# Ephys.net
KiCad netlist of a schematic drawn in EAGLE
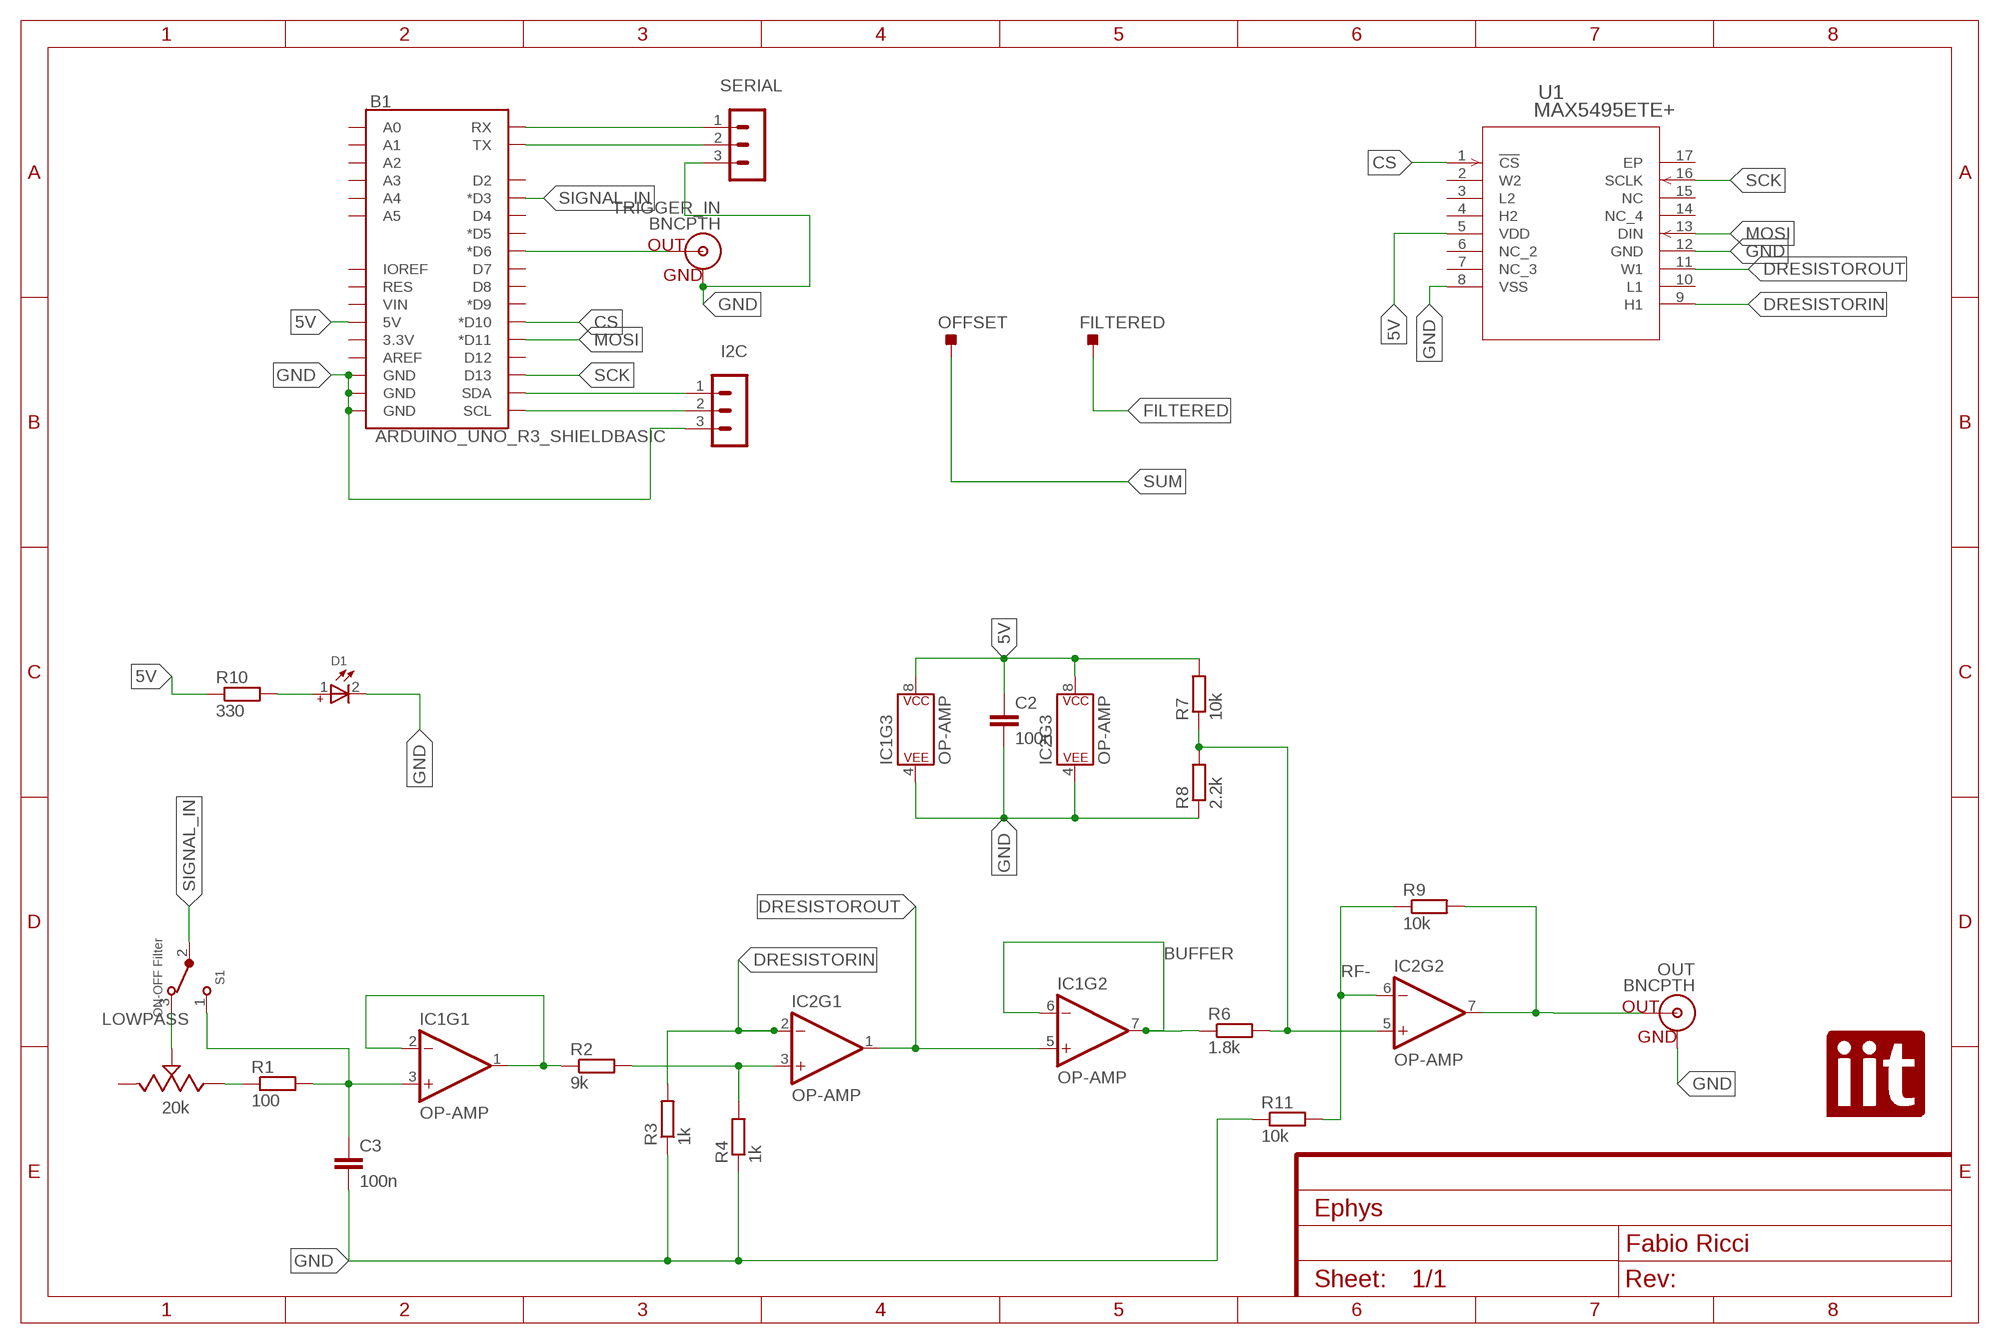
[diagram p0: schematic, sheet 1]

(export (version "E")
  (design (tool "Eeschema 10.0.6"))
  (components
    (comp (ref "B1")
      (value "ARDUINO_UNO_R3_SHIELDBASIC")
      (footprint "eagle-import:UNO_R3_SHIELD")
      (libsource (lib "eagle-import") (part "ARDUINO_UNO_R3_SHIELDBASIC"))
    )
    (comp (ref "C2")
      (value "100n")
      (footprint "eagle-import:C025-025X050")
      (libsource (lib "eagle-import") (part "C-EU025-025X050"))
    )
    (comp (ref "C3")
      (value "100n")
      (footprint "eagle-import:C025-025X050")
      (libsource (lib "eagle-import") (part "C-EU025-025X050"))
    )
    (comp (ref "D1")
      (value "WL-TMRC_3MM_151031SS04000_WITHOUTSTOPPER")
      (footprint "eagle-import:WL-TMRC_3MM")
      (libsource (lib "eagle-import") (part "WL-TMRC_3MM_WITHOUTSTOPPER_151031SS04000"))
    )
    (comp (ref "FILTERED")
      (value "TESTPOINT_TPS-PAD-036")
      (footprint "eagle-import:TESTPOINT_PAD-036")
      (libsource (lib "eagle-import") (part "TESTPOINT_TPS-PAD-036"))
    )
    (comp (ref "I2C")
      (value "MA03-1")
      (footprint "eagle-import:MA03-1")
      (libsource (lib "eagle-import") (part "MA03-1"))
    )
    (comp (ref "IC1")
      (value "OP-AMP")
      (footprint "eagle-import:DIP08")
      (libsource (lib "eagle-import") (part "OPAMP-DUALDIP"))
    )
    (comp (ref "IC2")
      (value "OP-AMP")
      (footprint "eagle-import:DIP08")
      (libsource (lib "eagle-import") (part "OPAMP-DUALDIP"))
    )
    (comp (ref "LOWPASS")
      (value "20k")
      (footprint "eagle-import:3362P-1-103LF")
      (fields
        (field (name "MANUFACTURER") "Bourns Inc.")
        (field (name "MPN") "3362P-1-103LF")
        (field (name "CREATED_PN") "PCBLayout.com")
      )
      (libsource (lib "eagle-import") (part "3362P-1-103LF"))
    )
    (comp (ref "OFFSET")
      (value "TESTPOINT_TPS-PAD-036")
      (footprint "eagle-import:TESTPOINT_PAD-036")
      (libsource (lib "eagle-import") (part "TESTPOINT_TPS-PAD-036"))
    )
    (comp (ref "OUT")
      (value "BNCPTH")
      (footprint "eagle-import:BNC")
      (libsource (lib "eagle-import") (part "BNCPTH"))
    )
    (comp (ref "R1")
      (value "100")
      (footprint "eagle-import:0204_7")
      (libsource (lib "eagle-import") (part "R-EU_0204/7"))
    )
    (comp (ref "R2")
      (value "9k")
      (footprint "eagle-import:0204_7")
      (libsource (lib "eagle-import") (part "R-EU_0204/7"))
    )
    (comp (ref "R3")
      (value "1k")
      (footprint "eagle-import:0204_7")
      (libsource (lib "eagle-import") (part "R-EU_0204/7"))
    )
    (comp (ref "R4")
      (value "1k")
      (footprint "eagle-import:0204_7")
      (libsource (lib "eagle-import") (part "R-EU_0204/7"))
    )
    (comp (ref "R6")
      (value "1.8k")
      (footprint "eagle-import:0204_7")
      (libsource (lib "eagle-import") (part "R-EU_0204/7"))
    )
    (comp (ref "R7")
      (value "10k")
      (footprint "eagle-import:0204_7")
      (libsource (lib "eagle-import") (part "R-EU_0204/7"))
    )
    (comp (ref "R8")
      (value "2.2k")
      (footprint "eagle-import:0204_7")
      (libsource (lib "eagle-import") (part "R-EU_0204/7"))
    )
    (comp (ref "R9")
      (value "10k")
      (footprint "eagle-import:0204_7")
      (libsource (lib "eagle-import") (part "R-EU_0204/7"))
    )
    (comp (ref "R10")
      (value "330")
      (footprint "eagle-import:0204_7")
      (libsource (lib "eagle-import") (part "R-EU_0204/7"))
    )
    (comp (ref "R11")
      (value "10k")
      (footprint "eagle-import:0204_7")
      (libsource (lib "eagle-import") (part "R-EU_0204/7"))
    )
    (comp (ref "S1")
      (value "ON-OFF Filter")
      (footprint "eagle-import:472121010111")
      (libsource (lib "eagle-import") (part "472121010111"))
    )
    (comp (ref "SERIAL")
      (value "MA03-1")
      (footprint "eagle-import:MA03-1")
      (libsource (lib "eagle-import") (part "MA03-1"))
    )
    (comp (ref "TRIGGER_IN")
      (value "BNCPTH")
      (footprint "eagle-import:BNC")
      (libsource (lib "eagle-import") (part "BNCPTH"))
    )
    (comp (ref "U$1")
      (value "LOGO")
      (footprint "eagle-import:IIT")
      (libsource (lib "eagle-import") (part "LOGO"))
    )
    (comp (ref "U1")
      (value "MAX5495ETE+")
      (footprint "eagle-import:21-0140_T1655+3_MXM")
      (fields (field (name "COPYRIGHT") "Copyright (C) 2024 Ultra Librarian. All rights reserved."))
      (libsource (lib "eagle-import") (part "MAX5495ETE+"))
    )
  )
  (nets
    (net (code "1") (name "/BUFFER") (class "Default")
      (node (ref "IC1") (pin "6") (pinfunction "-IN_6") (pintype "input"))
      (node (ref "IC1") (pin "7") (pinfunction "OUT_7") (pintype "output"))
      (node (ref "R6") (pin "1") (pinfunction "1_1") (pintype "passive"))
    )
    (net (code "2") (name "/RF-") (class "Default")
      (node (ref "IC2") (pin "6") (pinfunction "-IN_6") (pintype "input"))
      (node (ref "R11") (pin "2") (pinfunction "2_2") (pintype "passive"))
      (node (ref "R9") (pin "1") (pinfunction "1_1") (pintype "passive"))
    )
    (net (code "3") (name "5V") (class "Default")
      (node (ref "B1") (pin "5V") (pinfunction "5V_5V") (pintype "bidirectional"))
      (node (ref "C2") (pin "1") (pinfunction "1_1") (pintype "passive"))
      (node (ref "IC1") (pin "8") (pinfunction "P$V+_8") (pintype "bidirectional"))
      (node (ref "IC2") (pin "8") (pinfunction "P$V+_8") (pintype "bidirectional"))
      (node (ref "R10") (pin "1") (pinfunction "1_1") (pintype "passive"))
      (node (ref "R7") (pin "2") (pinfunction "2_2") (pintype "passive"))
      (node (ref "U1") (pin "5") (pinfunction "VDD_5") (pintype "power_in"))
    )
    (net (code "4") (name "CS") (class "Default")
      (node (ref "B1") (pin "D10") (pinfunction "*D10_D10") (pintype "bidirectional"))
      (node (ref "U1") (pin "1") (pinfunction "~{CS}_1") (pintype "input"))
    )
    (net (code "5") (name "DRESISTORIN") (class "Default")
      (node (ref "IC2") (pin "2") (pinfunction "-IN_2") (pintype "input"))
      (node (ref "R3") (pin "2") (pinfunction "2_2") (pintype "passive"))
      (node (ref "U1") (pin "9") (pinfunction "H1_9") (pintype "passive"))
    )
    (net (code "6") (name "DRESISTOROUT") (class "Default")
      (node (ref "IC1") (pin "5") (pinfunction "+IN_5") (pintype "input"))
      (node (ref "IC2") (pin "1") (pinfunction "OUT_1") (pintype "output"))
      (node (ref "U1") (pin "11") (pinfunction "W1_11") (pintype "passive"))
    )
    (net (code "7") (name "FILTERED") (class "Default")
      (node (ref "C3") (pin "1") (pinfunction "1_1") (pintype "passive"))
      (node (ref "FILTERED") (pin "1") (pinfunction "TP_1") (pintype "passive"))
      (node (ref "IC1") (pin "3") (pinfunction "+IN_3") (pintype "input"))
      (node (ref "R1") (pin "2") (pinfunction "2_2") (pintype "passive"))
      (node (ref "S1") (pin "1") (pinfunction "1_1") (pintype "passive"))
    )
    (net (code "8") (name "GND") (class "Default")
      (node (ref "B1") (pin "GND@0") (pinfunction "GND_GND@0") (pintype "bidirectional"))
      (node (ref "B1") (pin "GND@1") (pinfunction "GND_GND@1") (pintype "bidirectional"))
      (node (ref "B1") (pin "GND@2") (pinfunction "GND_GND@2") (pintype "bidirectional"))
      (node (ref "C2") (pin "2") (pinfunction "2_2") (pintype "passive"))
      (node (ref "C3") (pin "2") (pinfunction "2_2") (pintype "passive"))
      (node (ref "D1") (pin "2") (pinfunction "-_2") (pintype "passive"))
      (node (ref "I2C") (pin "3") (pinfunction "3_3") (pintype "passive"))
      (node (ref "IC1") (pin "4") (pinfunction "P$V-_4") (pintype "bidirectional"))
      (node (ref "IC2") (pin "4") (pinfunction "P$V-_4") (pintype "bidirectional"))
      (node (ref "OUT") (pin "GND") (pinfunction "GND_GND") (pintype "bidirectional"))
      (node (ref "R11") (pin "1") (pinfunction "1_1") (pintype "passive"))
      (node (ref "R3") (pin "1") (pinfunction "1_1") (pintype "passive"))
      (node (ref "R4") (pin "1") (pinfunction "1_1") (pintype "passive"))
      (node (ref "R8") (pin "1") (pinfunction "1_1") (pintype "passive"))
      (node (ref "SERIAL") (pin "3") (pinfunction "3_3") (pintype "passive"))
      (node (ref "TRIGGER_IN") (pin "GND") (pinfunction "GND_GND") (pintype "bidirectional"))
      (node (ref "U1") (pin "12") (pinfunction "GND_12") (pintype "power_in"))
      (node (ref "U1") (pin "8") (pinfunction "VSS_8") (pintype "power_in"))
    )
    (net (code "9") (name "MOSI") (class "Default")
      (node (ref "B1") (pin "D11") (pinfunction "*D11_D11") (pintype "bidirectional"))
      (node (ref "U1") (pin "13") (pinfunction "DIN_13") (pintype "input"))
    )
    (net (code "10") (name "Net-(B1-*D6)") (class "Default")
      (node (ref "B1") (pin "D6") (pinfunction "*D6_D6") (pintype "bidirectional"))
      (node (ref "TRIGGER_IN") (pin "S") (pinfunction "OUT_S") (pintype "bidirectional"))
    )
    (net (code "11") (name "Net-(B1-PadRX)") (class "Default")
      (node (ref "B1") (pin "RX") (pinfunction "RX_RX") (pintype "bidirectional"))
      (node (ref "SERIAL") (pin "1") (pinfunction "1_1") (pintype "passive"))
    )
    (net (code "12") (name "Net-(B1-PadSCL)") (class "Default")
      (node (ref "B1") (pin "SCL") (pinfunction "SCL_SCL") (pintype "bidirectional"))
      (node (ref "I2C") (pin "2") (pinfunction "2_2") (pintype "passive"))
    )
    (net (code "13") (name "Net-(B1-PadSDA)") (class "Default")
      (node (ref "B1") (pin "SDA") (pinfunction "SDA_SDA") (pintype "bidirectional"))
      (node (ref "I2C") (pin "1") (pinfunction "1_1") (pintype "passive"))
    )
    (net (code "14") (name "Net-(B1-PadTX)") (class "Default")
      (node (ref "B1") (pin "TX") (pinfunction "TX_TX") (pintype "bidirectional"))
      (node (ref "SERIAL") (pin "2") (pinfunction "2_2") (pintype "passive"))
    )
    (net (code "15") (name "Net-(D1-+)") (class "Default")
      (node (ref "D1") (pin "1") (pinfunction "+_1") (pintype "passive"))
      (node (ref "R10") (pin "2") (pinfunction "2_2") (pintype "passive"))
    )
    (net (code "16") (name "Net-(IC1A--IN)") (class "Default")
      (node (ref "IC1") (pin "1") (pinfunction "OUT_1") (pintype "output"))
      (node (ref "IC1") (pin "2") (pinfunction "-IN_2") (pintype "input"))
      (node (ref "R2") (pin "1") (pinfunction "1_1") (pintype "passive"))
    )
    (net (code "17") (name "Net-(IC2A-+IN)") (class "Default")
      (node (ref "IC2") (pin "3") (pinfunction "+IN_3") (pintype "input"))
      (node (ref "R2") (pin "2") (pinfunction "2_2") (pintype "passive"))
      (node (ref "R4") (pin "2") (pinfunction "2_2") (pintype "passive"))
    )
    (net (code "18") (name "Net-(IC2B-OUT)") (class "Default")
      (node (ref "IC2") (pin "7") (pinfunction "OUT_7") (pintype "output"))
      (node (ref "OUT") (pin "S") (pinfunction "OUT_S") (pintype "bidirectional"))
      (node (ref "R9") (pin "2") (pinfunction "2_2") (pintype "passive"))
    )
    (net (code "19") (name "Net-(LOWPASS-Pad2)") (class "Default")
      (node (ref "LOWPASS") (pin "2") (pinfunction "2_2") (pintype "passive"))
      (node (ref "S1") (pin "3") (pinfunction "3_3") (pintype "passive"))
    )
    (net (code "20") (name "Net-(LOWPASS-Pad3)") (class "Default")
      (node (ref "LOWPASS") (pin "3") (pinfunction "3_3") (pintype "passive"))
      (node (ref "R1") (pin "1") (pinfunction "1_1") (pintype "passive"))
    )
    (net (code "21") (name "SCK") (class "Default")
      (node (ref "B1") (pin "D13") (pinfunction "D13_D13") (pintype "bidirectional"))
      (node (ref "U1") (pin "16") (pinfunction "SCLK_16") (pintype "input"))
    )
    (net (code "22") (name "SIGNAL_IN") (class "Default")
      (node (ref "B1") (pin "D3") (pinfunction "*D3_D3") (pintype "bidirectional"))
      (node (ref "S1") (pin "2") (pinfunction "2_2") (pintype "passive"))
    )
    (net (code "23") (name "SUM") (class "Default")
      (node (ref "IC2") (pin "5") (pinfunction "+IN_5") (pintype "input"))
      (node (ref "OFFSET") (pin "1") (pinfunction "TP_1") (pintype "passive"))
      (node (ref "R6") (pin "2") (pinfunction "2_2") (pintype "passive"))
      (node (ref "R7") (pin "1") (pinfunction "1_1") (pintype "passive"))
      (node (ref "R8") (pin "2") (pinfunction "2_2") (pintype "passive"))
    )
    (net (code "24") (name "unconnected-(B1-*D5-PadD5)") (class "Default")
      (node (ref "B1") (pin "D5") (pinfunction "*D5_D5") (pintype "bidirectional"))
    )
    (net (code "25") (name "unconnected-(B1-*D9-PadD9)") (class "Default")
      (node (ref "B1") (pin "D9") (pinfunction "*D9_D9") (pintype "bidirectional"))
    )
    (net (code "26") (name "unconnected-(B1-Pad3.3V)") (class "Default")
      (node (ref "B1") (pin "3.3V") (pinfunction "3.3V_3.3V") (pintype "bidirectional"))
    )
    (net (code "27") (name "unconnected-(B1-PadA0)") (class "Default")
      (node (ref "B1") (pin "A0") (pinfunction "A0_A0") (pintype "bidirectional"))
    )
    (net (code "28") (name "unconnected-(B1-PadA1)") (class "Default")
      (node (ref "B1") (pin "A1") (pinfunction "A1_A1") (pintype "bidirectional"))
    )
    (net (code "29") (name "unconnected-(B1-PadA2)") (class "Default")
      (node (ref "B1") (pin "A2") (pinfunction "A2_A2") (pintype "bidirectional"))
    )
    (net (code "30") (name "unconnected-(B1-PadA3)") (class "Default")
      (node (ref "B1") (pin "A3") (pinfunction "A3_A3") (pintype "bidirectional"))
    )
    (net (code "31") (name "unconnected-(B1-PadA4)") (class "Default")
      (node (ref "B1") (pin "A4") (pinfunction "A4_A4") (pintype "bidirectional"))
    )
    (net (code "32") (name "unconnected-(B1-PadA5)") (class "Default")
      (node (ref "B1") (pin "A5") (pinfunction "A5_A5") (pintype "bidirectional"))
    )
    (net (code "33") (name "unconnected-(B1-PadAREF)") (class "Default")
      (node (ref "B1") (pin "AREF") (pinfunction "AREF_AREF") (pintype "bidirectional"))
    )
    (net (code "34") (name "unconnected-(B1-PadD2)") (class "Default")
      (node (ref "B1") (pin "D2") (pinfunction "D2_D2") (pintype "bidirectional"))
    )
    (net (code "35") (name "unconnected-(B1-PadD4)") (class "Default")
      (node (ref "B1") (pin "D4") (pinfunction "D4_D4") (pintype "bidirectional"))
    )
    (net (code "36") (name "unconnected-(B1-PadD7)") (class "Default")
      (node (ref "B1") (pin "D7") (pinfunction "D7_D7") (pintype "bidirectional"))
    )
    (net (code "37") (name "unconnected-(B1-PadD8)") (class "Default")
      (node (ref "B1") (pin "D8") (pinfunction "D8_D8") (pintype "bidirectional"))
    )
    (net (code "38") (name "unconnected-(B1-PadD12)") (class "Default")
      (node (ref "B1") (pin "D12") (pinfunction "D12_D12") (pintype "bidirectional"))
    )
    (net (code "39") (name "unconnected-(B1-PadIOREF)") (class "Default")
      (node (ref "B1") (pin "IOREF") (pinfunction "IOREF_IOREF") (pintype "bidirectional"))
    )
    (net (code "40") (name "unconnected-(B1-PadRES)") (class "Default")
      (node (ref "B1") (pin "RES") (pinfunction "RES_RES") (pintype "bidirectional"))
    )
    (net (code "41") (name "unconnected-(B1-PadVIN)") (class "Default")
      (node (ref "B1") (pin "VIN") (pinfunction "VIN_VIN") (pintype "bidirectional"))
    )
    (net (code "42") (name "unconnected-(LOWPASS-Pad1)") (class "Default")
      (node (ref "LOWPASS") (pin "1") (pinfunction "1_1") (pintype "passive"))
    )
    (net (code "43") (name "unconnected-(U1-EP-Pad17)") (class "Default")
      (node (ref "U1") (pin "17") (pinfunction "EP_17") (pintype "passive"))
    )
    (net (code "44") (name "unconnected-(U1-H2-Pad4)") (class "Default")
      (node (ref "U1") (pin "4") (pinfunction "H2_4") (pintype "passive"))
    )
    (net (code "45") (name "unconnected-(U1-L1-Pad10)") (class "Default")
      (node (ref "U1") (pin "10") (pinfunction "L1_10") (pintype "passive"))
    )
    (net (code "46") (name "unconnected-(U1-L2-Pad3)") (class "Default")
      (node (ref "U1") (pin "3") (pinfunction "L2_3") (pintype "passive"))
    )
    (net (code "47") (name "unconnected-(U1-NC-Pad15)") (class "Default")
      (node (ref "U1") (pin "15") (pinfunction "NC_15") (pintype "no_connect"))
    )
    (net (code "48") (name "unconnected-(U1-NC_2-Pad6)") (class "Default")
      (node (ref "U1") (pin "6") (pinfunction "NC_2_6") (pintype "no_connect"))
    )
    (net (code "49") (name "unconnected-(U1-NC_3-Pad7)") (class "Default")
      (node (ref "U1") (pin "7") (pinfunction "NC_3_7") (pintype "no_connect"))
    )
    (net (code "50") (name "unconnected-(U1-NC_4-Pad14)") (class "Default")
      (node (ref "U1") (pin "14") (pinfunction "NC_4_14") (pintype "no_connect"))
    )
    (net (code "51") (name "unconnected-(U1-W2-Pad2)") (class "Default")
      (node (ref "U1") (pin "2") (pinfunction "W2_2") (pintype "passive"))
    )
  )
)
